# MHBP-LCD-Adapter.net
KiCad netlist of a schematic drawn in EAGLE
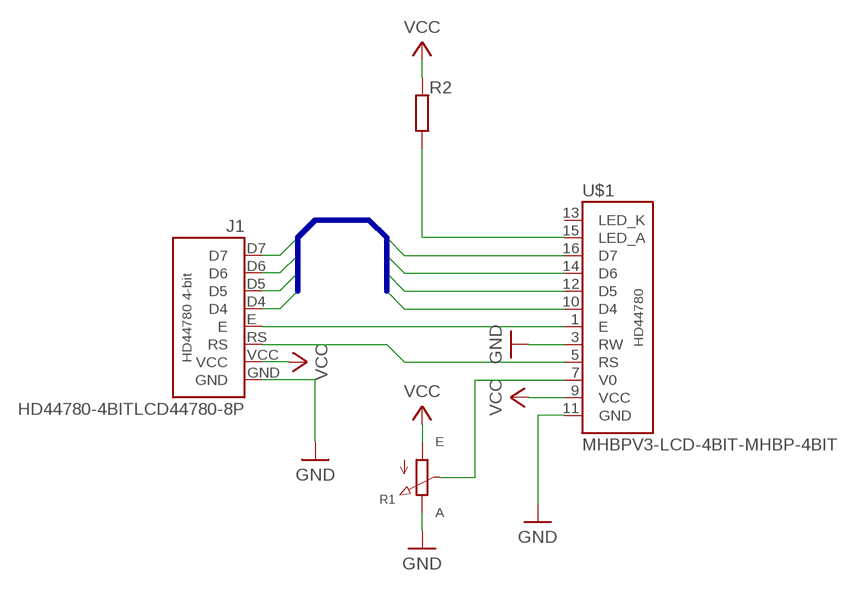
[diagram p0: schematic, sheet 1]

(export (version "E")
  (design (tool "Eeschema 10.0.6"))
  (components
    (comp (ref "J1")
      (value "HD44780-4BITLCD44780-8P")
      (footprint "eagle-import:CONN-LCD44780")
      (libsource (lib "eagle-import") (part "HD44780-4BITLCD44780-8P"))
    )
    (comp (ref "R1")
      (value "POT-V")
      (footprint "eagle-import:POT-V")
      (libsource (lib "eagle-import") (part "POT-V"))
    )
    (comp (ref "R2")
      (value "R0207/12")
      (footprint "eagle-import:0207_12")
      (libsource (lib "eagle-import") (part "R0207/12"))
    )
    (comp (ref "U$1")
      (value "MHBPV3-LCD-4BIT-MHBP-4BIT")
      (footprint "eagle-import:MBHP-LCD-4BIT")
      (libsource (lib "eagle-import") (part "MHBPV3-LCD-4BIT-MHBP-4BIT"))
    )
  )
  (nets
    (net (code "1") (name "/D4") (class "Default")
      (node (ref "J1") (pin "D4") (pinfunction "D4_D4") (pintype "passive"))
      (node (ref "U$1") (pin "10") (pinfunction "D4_10") (pintype "passive"))
    )
    (net (code "2") (name "/D5") (class "Default")
      (node (ref "J1") (pin "D5") (pinfunction "D5_D5") (pintype "passive"))
      (node (ref "U$1") (pin "12") (pinfunction "D5_12") (pintype "passive"))
    )
    (net (code "3") (name "/D6") (class "Default")
      (node (ref "J1") (pin "D6") (pinfunction "D6_D6") (pintype "passive"))
      (node (ref "U$1") (pin "14") (pinfunction "D6_14") (pintype "passive"))
    )
    (net (code "4") (name "/D7") (class "Default")
      (node (ref "J1") (pin "D7") (pinfunction "D7_D7") (pintype "passive"))
      (node (ref "U$1") (pin "16") (pinfunction "D7_16") (pintype "passive"))
    )
    (net (code "5") (name "GND") (class "Default")
      (node (ref "J1") (pin "GND") (pinfunction "GND_GND") (pintype "passive"))
      (node (ref "R1") (pin "E") (pinfunction "E_E") (pintype "passive"))
      (node (ref "U$1") (pin "11") (pinfunction "GND_11") (pintype "passive"))
      (node (ref "U$1") (pin "3") (pinfunction "RW_3") (pintype "passive"))
    )
    (net (code "6") (name "Net-(U$1-E)") (class "Default")
      (node (ref "J1") (pin "E") (pinfunction "E_E") (pintype "passive"))
      (node (ref "U$1") (pin "1") (pinfunction "E_1") (pintype "passive"))
    )
    (net (code "7") (name "Net-(U$1-LED_A)") (class "Default")
      (node (ref "R2") (pin "1") (pinfunction "1_1") (pintype "passive"))
      (node (ref "U$1") (pin "15") (pinfunction "LED_A_15") (pintype "passive"))
    )
    (net (code "8") (name "Net-(U$1-RS)") (class "Default")
      (node (ref "J1") (pin "RS") (pinfunction "RS_RS") (pintype "passive"))
      (node (ref "U$1") (pin "5") (pinfunction "RS_5") (pintype "passive"))
    )
    (net (code "9") (name "Net-(U$1-V0)") (class "Default")
      (node (ref "R1") (pin "S") (pinfunction "S_S") (pintype "passive"))
      (node (ref "U$1") (pin "7") (pinfunction "V0_7") (pintype "passive"))
    )
    (net (code "10") (name "VCC") (class "Default")
      (node (ref "J1") (pin "VCC") (pinfunction "VCC_VCC") (pintype "passive"))
      (node (ref "R1") (pin "A") (pinfunction "A_A") (pintype "passive"))
      (node (ref "R2") (pin "2") (pinfunction "2_2") (pintype "passive"))
      (node (ref "U$1") (pin "9") (pinfunction "VCC_9") (pintype "passive"))
    )
    (net (code "11") (name "unconnected-(U$1-LED_K-Pad13)") (class "Default")
      (node (ref "U$1") (pin "13") (pinfunction "LED_K_13") (pintype "passive"))
    )
  )
)
